# VarmoEmergencyStop_-_Rev_A1.net
KiCad netlist of a schematic drawn in EAGLE
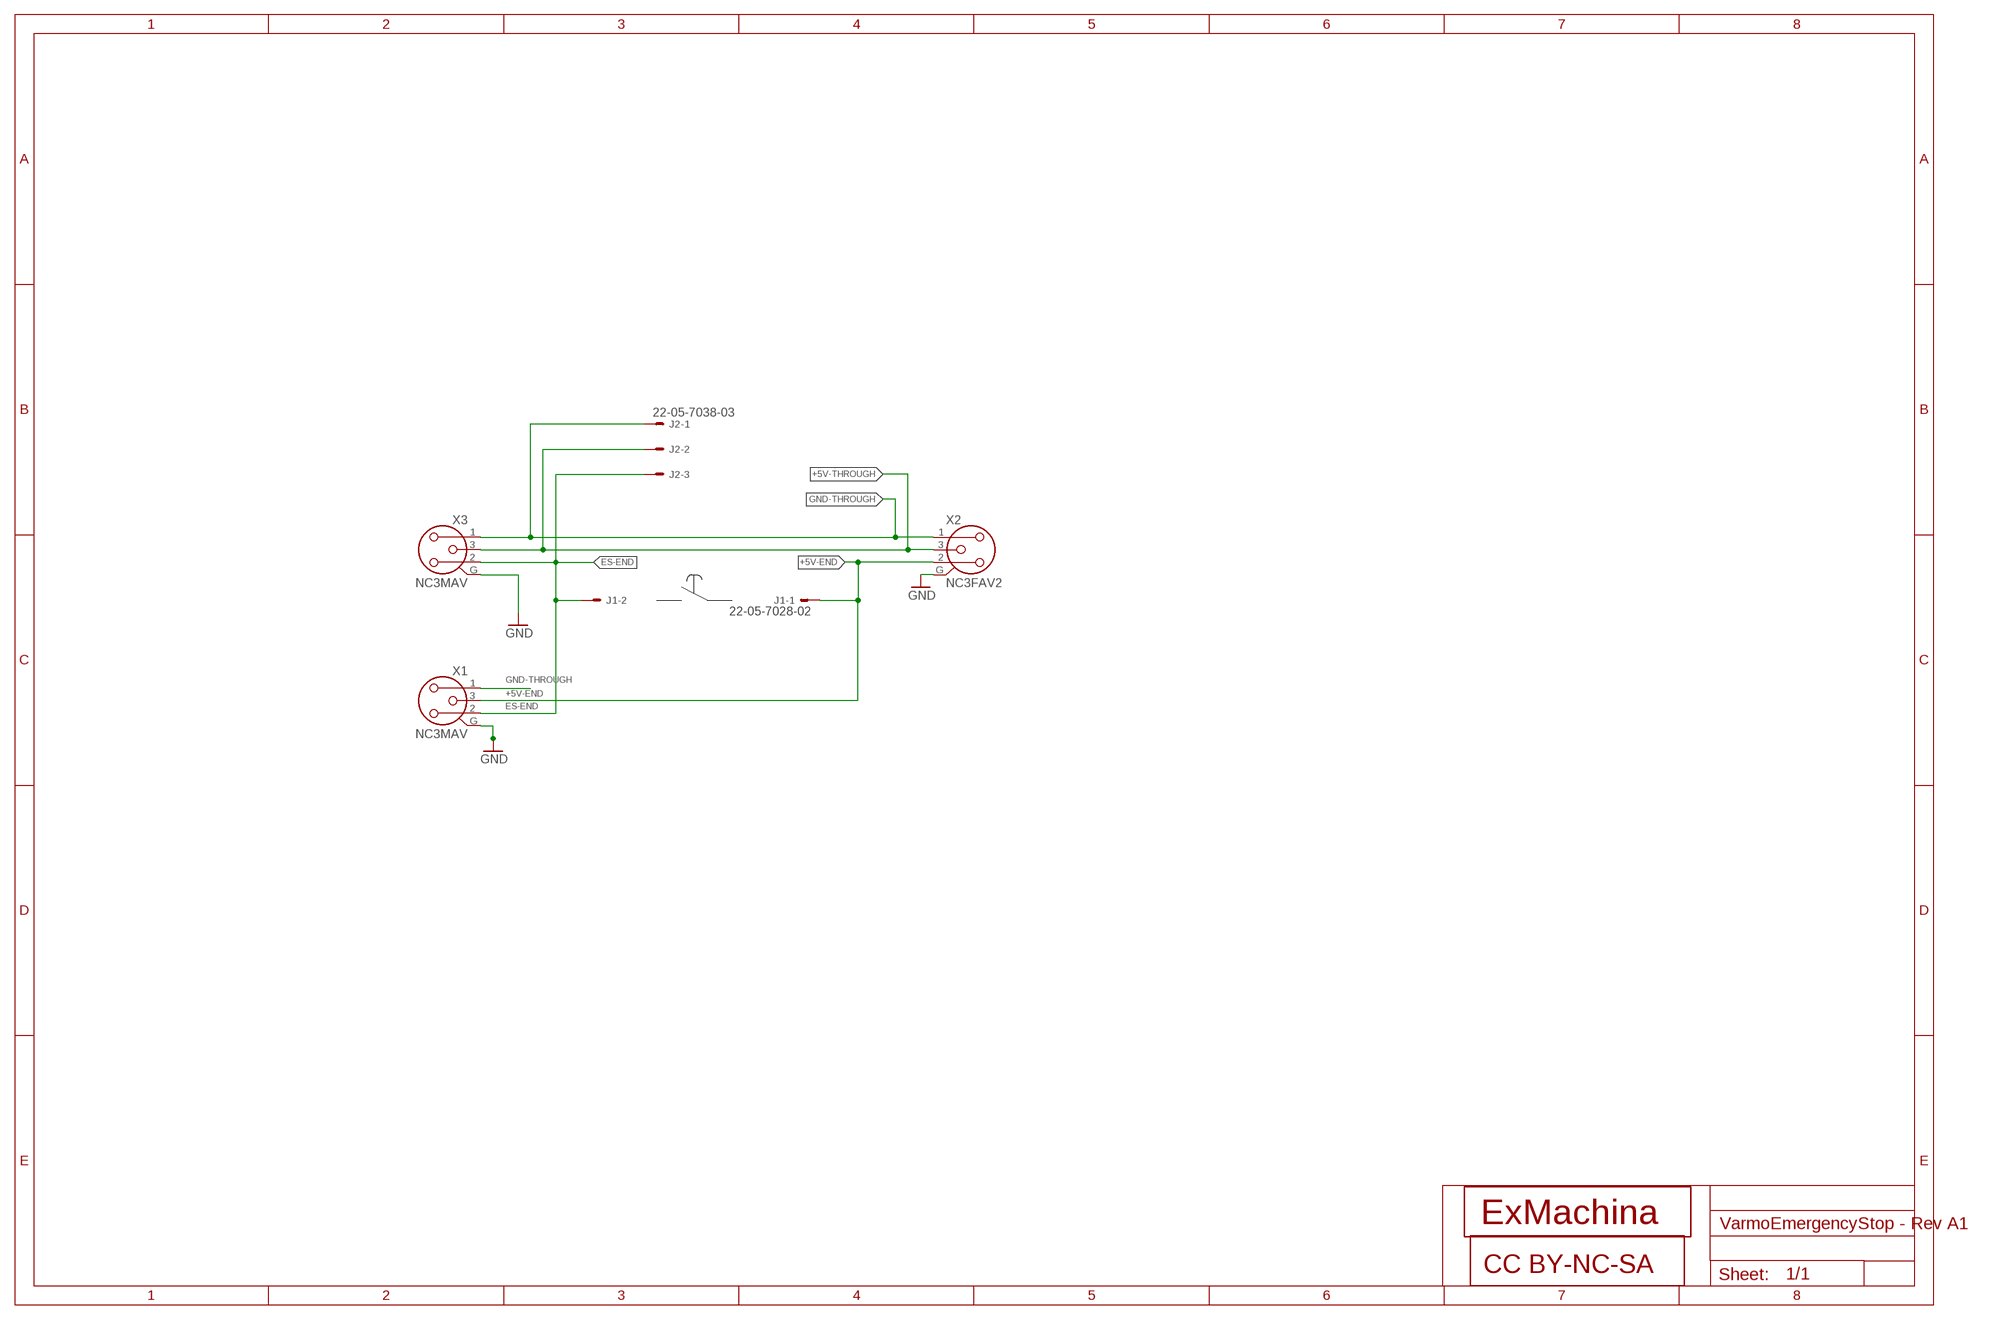
[diagram p0: schematic, sheet 1]

(export (version "E")
  (design (tool "Eeschema 10.0.6"))
  (components
    (comp (ref "J1")
      (value "22-05-7028-02")
      (footprint "eagle-import:7395-02")
      (libsource (lib "eagle-import") (part "22-?-0205-7028"))
    )
    (comp (ref "J2")
      (value "22-05-7038-03")
      (footprint "eagle-import:7395-03")
      (libsource (lib "eagle-import") (part "22-?-0305-7038"))
    )
    (comp (ref "U$1")
      (value "EXMACHINA-LOGO-NAME")
      (footprint "eagle-import:EXM-LOGO-BASELINE")
      (libsource (lib "eagle-import") (part "EXMACHINA-LOGO-NAME"))
    )
    (comp (ref "U$2")
      (value "CC-BY-NC-SA")
      (footprint "eagle-import:CC-BY-NC-SA")
      (libsource (lib "eagle-import") (part "CC-BY-NC-SA"))
    )
    (comp (ref "X1")
      (value "NC3MAV")
      (footprint "eagle-import:NC3MAV")
      (fields (field (name "MF") "FARNELL"))
      (libsource (lib "eagle-import") (part "NC3MAV"))
    )
    (comp (ref "X2")
      (value "NC3FAV2")
      (footprint "eagle-import:NC3FAV2")
      (fields (field (name "MF") "NEUTRIK"))
      (libsource (lib "eagle-import") (part "NC3FAV2"))
    )
    (comp (ref "X3")
      (value "NC3MAV")
      (footprint "eagle-import:NC3MAV")
      (fields (field (name "MF") "FARNELL"))
      (libsource (lib "eagle-import") (part "NC3MAV"))
    )
  )
  (nets
    (net (code "1") (name "+5V-END") (class "Default")
      (node (ref "J1") (pin "1") (pinfunction "S_1") (pintype "passive"))
      (node (ref "X1") (pin "3") (pinfunction "3_3") (pintype "passive"))
      (node (ref "X2") (pin "2") (pinfunction "2_2") (pintype "passive"))
    )
    (net (code "2") (name "+5V-THROUGH") (class "Default")
      (node (ref "J2") (pin "2") (pinfunction "S_2") (pintype "passive"))
      (node (ref "X2") (pin "3") (pinfunction "3_3") (pintype "passive"))
      (node (ref "X3") (pin "3") (pinfunction "3_3") (pintype "passive"))
    )
    (net (code "3") (name "ES-END") (class "Default")
      (node (ref "J1") (pin "2") (pinfunction "S_2") (pintype "passive"))
      (node (ref "J2") (pin "3") (pinfunction "S_3") (pintype "passive"))
      (node (ref "X1") (pin "2") (pinfunction "2_2") (pintype "passive"))
      (node (ref "X3") (pin "2") (pinfunction "2_2") (pintype "passive"))
    )
    (net (code "4") (name "GND") (class "Default")
      (node (ref "X1") (pin "G") (pinfunction "G_G") (pintype "passive"))
      (node (ref "X2") (pin "G") (pinfunction "G_G") (pintype "passive"))
      (node (ref "X3") (pin "G") (pinfunction "G_G") (pintype "passive"))
    )
    (net (code "5") (name "GND-THROUGH") (class "Default")
      (node (ref "J2") (pin "1") (pinfunction "S_1") (pintype "passive"))
      (node (ref "X1") (pin "1") (pinfunction "1_1") (pintype "passive"))
      (node (ref "X2") (pin "1") (pinfunction "1_1") (pintype "passive"))
      (node (ref "X3") (pin "1") (pinfunction "1_1") (pintype "passive"))
    )
  )
)
